# BAT.net
KiCad netlist of a schematic drawn in Altium Designer
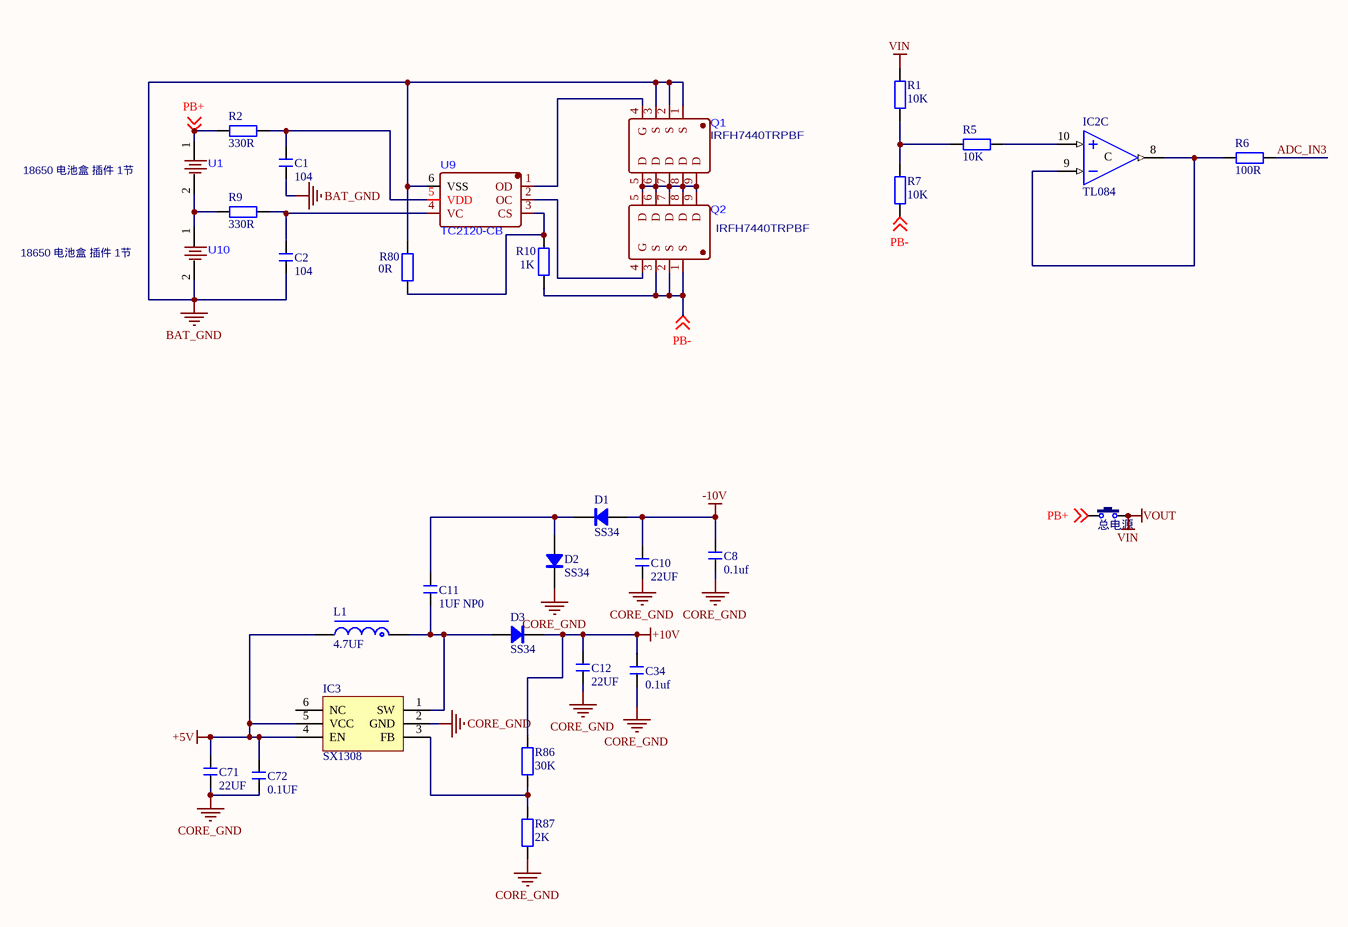
[diagram p0: BAT.SchDoc]

(export (version "E")
  (design (tool "Eeschema 10.0.6"))
  (components
    (comp (ref "C1")
      (value "104")
      (footprint "C 0805_L")
      (description "无极性贴片电容")
      (fields (field (name "版权归属") "源创客"))
      (libsource (lib "3.1   - 电阻-电容-电感") (part "C"))
    )
    (comp (ref "C2")
      (value "104")
      (footprint "C 0805_L")
      (description "无极性贴片电容")
      (fields (field (name "版权归属") "源创客"))
      (libsource (lib "3.1   - 电阻-电容-电感") (part "C"))
    )
    (comp (ref "C8")
      (value "0.1uf")
      (footprint "C 0805_L")
      (description "无极性贴片电容")
      (fields (field (name "版权归属") "源创客"))
      (libsource (lib "3.1   - 电阻-电容-电感") (part "C"))
    )
    (comp (ref "C10")
      (value "22UF")
      (footprint "C 0805_L")
      (description "无极性贴片电容")
      (fields (field (name "版权归属") "源创客"))
      (libsource (lib "3.1   - 电阻-电容-电感") (part "C"))
    )
    (comp (ref "C11")
      (value "1UF NP0")
      (footprint "C 0805_L")
      (description "无极性贴片电容")
      (fields (field (name "版权归属") "源创客"))
      (libsource (lib "3.1   - 电阻-电容-电感") (part "C"))
    )
    (comp (ref "C12")
      (value "22UF")
      (footprint "C 0805_L")
      (description "无极性贴片电容")
      (fields (field (name "版权归属") "源创客"))
      (libsource (lib "3.1   - 电阻-电容-电感") (part "C"))
    )
    (comp (ref "C34")
      (value "0.1uf")
      (footprint "C 0805_L")
      (description "无极性贴片电容")
      (fields (field (name "版权归属") "源创客"))
      (libsource (lib "3.1   - 电阻-电容-电感") (part "C"))
    )
    (comp (ref "C71")
      (value "22UF")
      (footprint "C 0805_L")
      (description "无极性贴片电容")
      (fields (field (name "版权归属") "源创客"))
      (libsource (lib "3.1   - 电阻-电容-电感") (part "C"))
    )
    (comp (ref "C72")
      (value "0.1UF")
      (footprint "C 0805_L")
      (description "无极性贴片电容")
      (fields (field (name "版权归属") "源创客"))
      (libsource (lib "3.1   - 电阻-电容-电感") (part "C"))
    )
    (comp (ref "D1")
      (value "SS34")
      (footprint "SOD-123F")
      (description "肖特基二极管")
      (fields (field (name "版权归属") "源创客"))
      (libsource (lib "8.1   - 二极管-整流桥") (part "SS34"))
    )
    (comp (ref "D2")
      (value "SS34")
      (footprint "SOD-123F")
      (description "肖特基二极管")
      (fields (field (name "版权归属") "源创客"))
      (libsource (lib "8.1   - 二极管-整流桥") (part "SS34"))
    )
    (comp (ref "D3")
      (value "SS34")
      (footprint "SOD-123F")
      (description "肖特基二极管")
      (fields (field (name "版权归属") "源创客"))
      (libsource (lib "8.1   - 二极管-整流桥") (part "SS34"))
    )
    (comp (ref "IC2")
      (value "TL084")
      (footprint "SOP14_N")
      (description "4路运放")
      (fields (field (name "版权归属") "源创客"))
      (libsource (lib "1.5   - 运放-功放") (part "TL084"))
    )
    (comp (ref "IC3")
      (value "SX1308")
      (footprint "SOT23-6N")
      (description "可调升压芯片")
      (fields (field (name "版权归属") "源创客"))
      (libsource (lib "1.3   - 电源类芯片") (part "SX1308"))
    )
    (comp (ref "L1")
      (value "4.7UF")
      (footprint "L-SMD-0420")
      (description "功率屏蔽电感")
      (fields (field (name "版权归属") "源创客"))
      (libsource (lib "3.1   - 电阻-电容-电感") (part "L-CDRH"))
    )
    (comp (ref "Q1")
      (value "IRFH7440TRPBF")
      (footprint "PQFN-8P_L5.8-W4.9-P1.27-LS6.0-BL")
      (libsource (lib "IRFH7440TRPBF") (part "IRFH7440TRPBF"))
    )
    (comp (ref "Q2")
      (value "IRFH7440TRPBF")
      (footprint "PQFN-8P_L5.8-W4.9-P1.27-LS6.0-BL")
      (libsource (lib "IRFH7440TRPBF") (part "IRFH7440TRPBF"))
    )
    (comp (ref "R1")
      (value "10K")
      (footprint "R 0805_L")
      (description "贴片电阻")
      (fields (field (name "版权归属") "源创客"))
      (libsource (lib "3.1   - 电阻-电容-电感") (part "R"))
    )
    (comp (ref "R2")
      (value "330R")
      (footprint "R 0805_L")
      (description "贴片电阻")
      (fields (field (name "版权归属") "源创客"))
      (libsource (lib "3.1   - 电阻-电容-电感") (part "R"))
    )
    (comp (ref "R5")
      (value "10K")
      (footprint "R 0805_L")
      (description "贴片电阻")
      (fields (field (name "版权归属") "源创客"))
      (libsource (lib "3.1   - 电阻-电容-电感") (part "R"))
    )
    (comp (ref "R6")
      (value "100R")
      (footprint "R 0805_L")
      (description "贴片电阻")
      (fields (field (name "版权归属") "源创客"))
      (libsource (lib "3.1   - 电阻-电容-电感") (part "R"))
    )
    (comp (ref "R7")
      (value "10K")
      (footprint "R 0805_L")
      (description "贴片电阻")
      (fields (field (name "版权归属") "源创客"))
      (libsource (lib "3.1   - 电阻-电容-电感") (part "R"))
    )
    (comp (ref "R9")
      (value "330R")
      (footprint "R 0805_L")
      (description "贴片电阻")
      (fields (field (name "版权归属") "源创客"))
      (libsource (lib "3.1   - 电阻-电容-电感") (part "R"))
    )
    (comp (ref "R10")
      (value "1K")
      (footprint "R 0805_L")
      (description "贴片电阻")
      (fields (field (name "版权归属") "源创客"))
      (libsource (lib "3.1   - 电阻-电容-电感") (part "R"))
    )
    (comp (ref "R80")
      (value "0R")
      (footprint "R 0805_L")
      (description "贴片电阻")
      (fields (field (name "版权归属") "源创客"))
      (libsource (lib "3.1   - 电阻-电容-电感") (part "R"))
    )
    (comp (ref "R86")
      (value "30K")
      (footprint "R 0805_L")
      (description "贴片电阻")
      (fields (field (name "版权归属") "源创客"))
      (libsource (lib "3.1   - 电阻-电容-电感") (part "R"))
    )
    (comp (ref "R87")
      (value "2K")
      (footprint "R 0805_L")
      (description "贴片电阻")
      (fields (field (name "版权归属") "源创客"))
      (libsource (lib "3.1   - 电阻-电容-电感") (part "R"))
    )
    (comp (ref "U1")
      (value "18650 电池盒 插件 1节")
      (footprint "BAT-TH_18650-C9900004923")
      (libsource (lib "18650 电池盒 插件 1节") (part "18650 电池盒 插件 1节"))
    )
    (comp (ref "U9")
      (value "TC2120-CB")
      (footprint "SOT23-6L")
      (libsource (lib "TC2120-CB") (part "TC2120-CB"))
    )
    (comp (ref "U10")
      (value "18650 电池盒 插件 1节")
      (footprint "BAT-TH_18650-C9900004923")
      (libsource (lib "18650 电池盒 插件 1节") (part "18650 电池盒 插件 1节"))
    )
    (comp (ref "总电源")
      (value "6x6x5")
      (footprint "KEY-TH_CN-KCD11")
      (description "2脚直插6x6轻触开关")
      (fields (field (name "版权归属") "源创客"))
      (libsource (lib "5.1   - 按键-开关") (part "TSW DIP-2Pin-6x6"))
    )
  )
  (nets
    (net (code "1") (name "+5V") (class "Default")
      (node (ref "C71") (pin "1") (pinfunction "1_1") (pintype "passive"))
      (node (ref "C72") (pin "1") (pinfunction "1_1") (pintype "passive"))
      (node (ref "IC3") (pin "4") (pinfunction "EN_4") (pintype "passive"))
      (node (ref "IC3") (pin "5") (pinfunction "VCC_5") (pintype "passive"))
      (node (ref "L1") (pin "2") (pinfunction "2_2") (pintype "passive"))
    )
    (net (code "2") (name "+10V") (class "Default")
      (node (ref "C12") (pin "1") (pinfunction "1_1") (pintype "passive"))
      (node (ref "C34") (pin "1") (pinfunction "1_1") (pintype "passive"))
      (node (ref "D3") (pin "2") (pinfunction "K_2") (pintype "passive"))
      (node (ref "R86") (pin "1") (pinfunction "1_1") (pintype "passive"))
    )
    (net (code "3") (name "-10V") (class "Default")
      (node (ref "C10") (pin "1") (pinfunction "1_1") (pintype "passive"))
      (node (ref "C8") (pin "1") (pinfunction "1_1") (pintype "passive"))
      (node (ref "D1") (pin "1") (pinfunction "A_1") (pintype "passive"))
    )
    (net (code "4") (name "/ADC_IN3") (class "Default")
      (node (ref "R6") (pin "1") (pinfunction "1_1") (pintype "passive"))
    )
    (net (code "5") (name "BAT_GND") (class "Default")
      (node (ref "C1") (pin "1") (pinfunction "1_1") (pintype "passive"))
      (node (ref "C2") (pin "1") (pinfunction "1_1") (pintype "passive"))
      (node (ref "Q1") (pin "1") (pinfunction "S_1") (pintype "passive"))
      (node (ref "Q1") (pin "2") (pinfunction "S_2") (pintype "passive"))
      (node (ref "Q1") (pin "3") (pinfunction "S_3") (pintype "passive"))
      (node (ref "R80") (pin "1") (pinfunction "1_1") (pintype "passive"))
      (node (ref "U10") (pin "2") (pinfunction "2_2") (pintype "passive"))
      (node (ref "U9") (pin "6") (pinfunction "VSS_6") (pintype "passive"))
    )
    (net (code "6") (name "CORE_GND") (class "Default")
      (node (ref "C10") (pin "2") (pinfunction "2_2") (pintype "passive"))
      (node (ref "C12") (pin "2") (pinfunction "2_2") (pintype "passive"))
      (node (ref "C34") (pin "2") (pinfunction "2_2") (pintype "passive"))
      (node (ref "C71") (pin "2") (pinfunction "2_2") (pintype "passive"))
      (node (ref "C72") (pin "2") (pinfunction "2_2") (pintype "passive"))
      (node (ref "C8") (pin "2") (pinfunction "2_2") (pintype "passive"))
      (node (ref "D2") (pin "2") (pinfunction "K_2") (pintype "passive"))
      (node (ref "IC3") (pin "2") (pinfunction "GND_2") (pintype "passive"))
      (node (ref "R87") (pin "2") (pinfunction "2_2") (pintype "passive"))
    )
    (net (code "7") (name "Net-(D1-K)") (class "Default")
      (node (ref "C11") (pin "1") (pinfunction "1_1") (pintype "passive"))
      (node (ref "D1") (pin "2") (pinfunction "K_2") (pintype "passive"))
      (node (ref "D2") (pin "1") (pinfunction "A_1") (pintype "passive"))
    )
    (net (code "8") (name "Net-(D3-A)") (class "Default")
      (node (ref "C11") (pin "2") (pinfunction "2_2") (pintype "passive"))
      (node (ref "D3") (pin "1") (pinfunction "A_1") (pintype "passive"))
      (node (ref "IC3") (pin "1") (pinfunction "SW_1") (pintype "passive"))
      (node (ref "L1") (pin "1") (pinfunction "1_1") (pintype "passive"))
    )
    (net (code "9") (name "Net-(IC2C-IN+)") (class "Default")
      (node (ref "IC2") (pin "10") (pinfunction "IN+_10") (pintype "input"))
      (node (ref "R5") (pin "1") (pinfunction "1_1") (pintype "passive"))
    )
    (net (code "10") (name "Net-(IC2C-IN-)") (class "Default")
      (node (ref "IC2") (pin "8") (pinfunction "OUT_8") (pintype "output"))
      (node (ref "IC2") (pin "9") (pinfunction "IN-_9") (pintype "input"))
      (node (ref "R6") (pin "2") (pinfunction "2_2") (pintype "passive"))
    )
    (net (code "11") (name "Net-(IC3-FB)") (class "Default")
      (node (ref "IC3") (pin "3") (pinfunction "FB_3") (pintype "passive"))
      (node (ref "R86") (pin "2") (pinfunction "2_2") (pintype "passive"))
      (node (ref "R87") (pin "1") (pinfunction "1_1") (pintype "passive"))
    )
    (net (code "12") (name "Net-(Q1-D-Pad5)") (class "Default")
      (node (ref "Q1") (pin "5") (pinfunction "D_5") (pintype "passive"))
      (node (ref "Q1") (pin "6") (pinfunction "D_6") (pintype "passive"))
      (node (ref "Q1") (pin "7") (pinfunction "D_7") (pintype "passive"))
      (node (ref "Q1") (pin "8") (pinfunction "D_8") (pintype "passive"))
      (node (ref "Q1") (pin "9") (pinfunction "D_9") (pintype "passive"))
      (node (ref "Q2") (pin "5") (pinfunction "D_5") (pintype "passive"))
      (node (ref "Q2") (pin "6") (pinfunction "D_6") (pintype "passive"))
      (node (ref "Q2") (pin "7") (pinfunction "D_7") (pintype "passive"))
      (node (ref "Q2") (pin "8") (pinfunction "D_8") (pintype "passive"))
      (node (ref "Q2") (pin "9") (pinfunction "D_9") (pintype "passive"))
    )
    (net (code "13") (name "Net-(Q1-G)") (class "Default")
      (node (ref "Q1") (pin "4") (pinfunction "G_4") (pintype "passive"))
      (node (ref "U9") (pin "1") (pinfunction "OD_1") (pintype "passive"))
    )
    (net (code "14") (name "Net-(Q2-G)") (class "Default")
      (node (ref "Q2") (pin "4") (pinfunction "G_4") (pintype "passive"))
      (node (ref "U9") (pin "2") (pinfunction "OC_2") (pintype "passive"))
    )
    (net (code "15") (name "Net-(R1-Pad2)") (class "Default")
      (node (ref "R1") (pin "2") (pinfunction "2_2") (pintype "passive"))
      (node (ref "R5") (pin "2") (pinfunction "2_2") (pintype "passive"))
      (node (ref "R7") (pin "1") (pinfunction "1_1") (pintype "passive"))
    )
    (net (code "16") (name "Net-(R9-Pad2)") (class "Default")
      (node (ref "R9") (pin "2") (pinfunction "2_2") (pintype "passive"))
      (node (ref "U1") (pin "2") (pinfunction "2_2") (pintype "passive"))
      (node (ref "U10") (pin "1") (pinfunction "1_1") (pintype "passive"))
    )
    (net (code "17") (name "Net-(U9-CS)") (class "Default")
      (node (ref "R10") (pin "1") (pinfunction "1_1") (pintype "passive"))
      (node (ref "R80") (pin "2") (pinfunction "2_2") (pintype "passive"))
      (node (ref "U9") (pin "3") (pinfunction "CS_3") (pintype "passive"))
    )
    (net (code "18") (name "Net-(U9-VC)") (class "Default")
      (node (ref "C2") (pin "2") (pinfunction "2_2") (pintype "passive"))
      (node (ref "R9") (pin "1") (pinfunction "1_1") (pintype "passive"))
      (node (ref "U9") (pin "4") (pinfunction "VC_4") (pintype "passive"))
    )
    (net (code "19") (name "Net-(U9-VDD)") (class "Default")
      (node (ref "C1") (pin "2") (pinfunction "2_2") (pintype "passive"))
      (node (ref "R2") (pin "1") (pinfunction "1_1") (pintype "passive"))
      (node (ref "U9") (pin "5") (pinfunction "VDD_5") (pintype "passive"))
    )
    (net (code "20") (name "PB+") (class "Default")
      (node (ref "R2") (pin "2") (pinfunction "2_2") (pintype "passive"))
      (node (ref "U1") (pin "1") (pinfunction "1_1") (pintype "passive"))
      (node (ref "总电源") (pin "1") (pinfunction "1_1") (pintype "passive"))
    )
    (net (code "21") (name "PB-") (class "Default")
      (node (ref "Q2") (pin "1") (pinfunction "S_1") (pintype "passive"))
      (node (ref "Q2") (pin "2") (pinfunction "S_2") (pintype "passive"))
      (node (ref "Q2") (pin "3") (pinfunction "S_3") (pintype "passive"))
      (node (ref "R10") (pin "2") (pinfunction "2_2") (pintype "passive"))
      (node (ref "R7") (pin "2") (pinfunction "2_2") (pintype "passive"))
    )
    (net (code "22") (name "VIN") (class "Default")
      (node (ref "R1") (pin "1") (pinfunction "1_1") (pintype "passive"))
      (node (ref "总电源") (pin "2") (pinfunction "2_2") (pintype "passive"))
    )
    (net (code "23") (name "unconnected-(IC3-NC-Pad6)") (class "Default")
      (node (ref "IC3") (pin "6") (pinfunction "NC_6") (pintype "passive"))
    )
  )
)
